# Pi_Zero_PITS.net
KiCad netlist of a schematic drawn in EAGLE
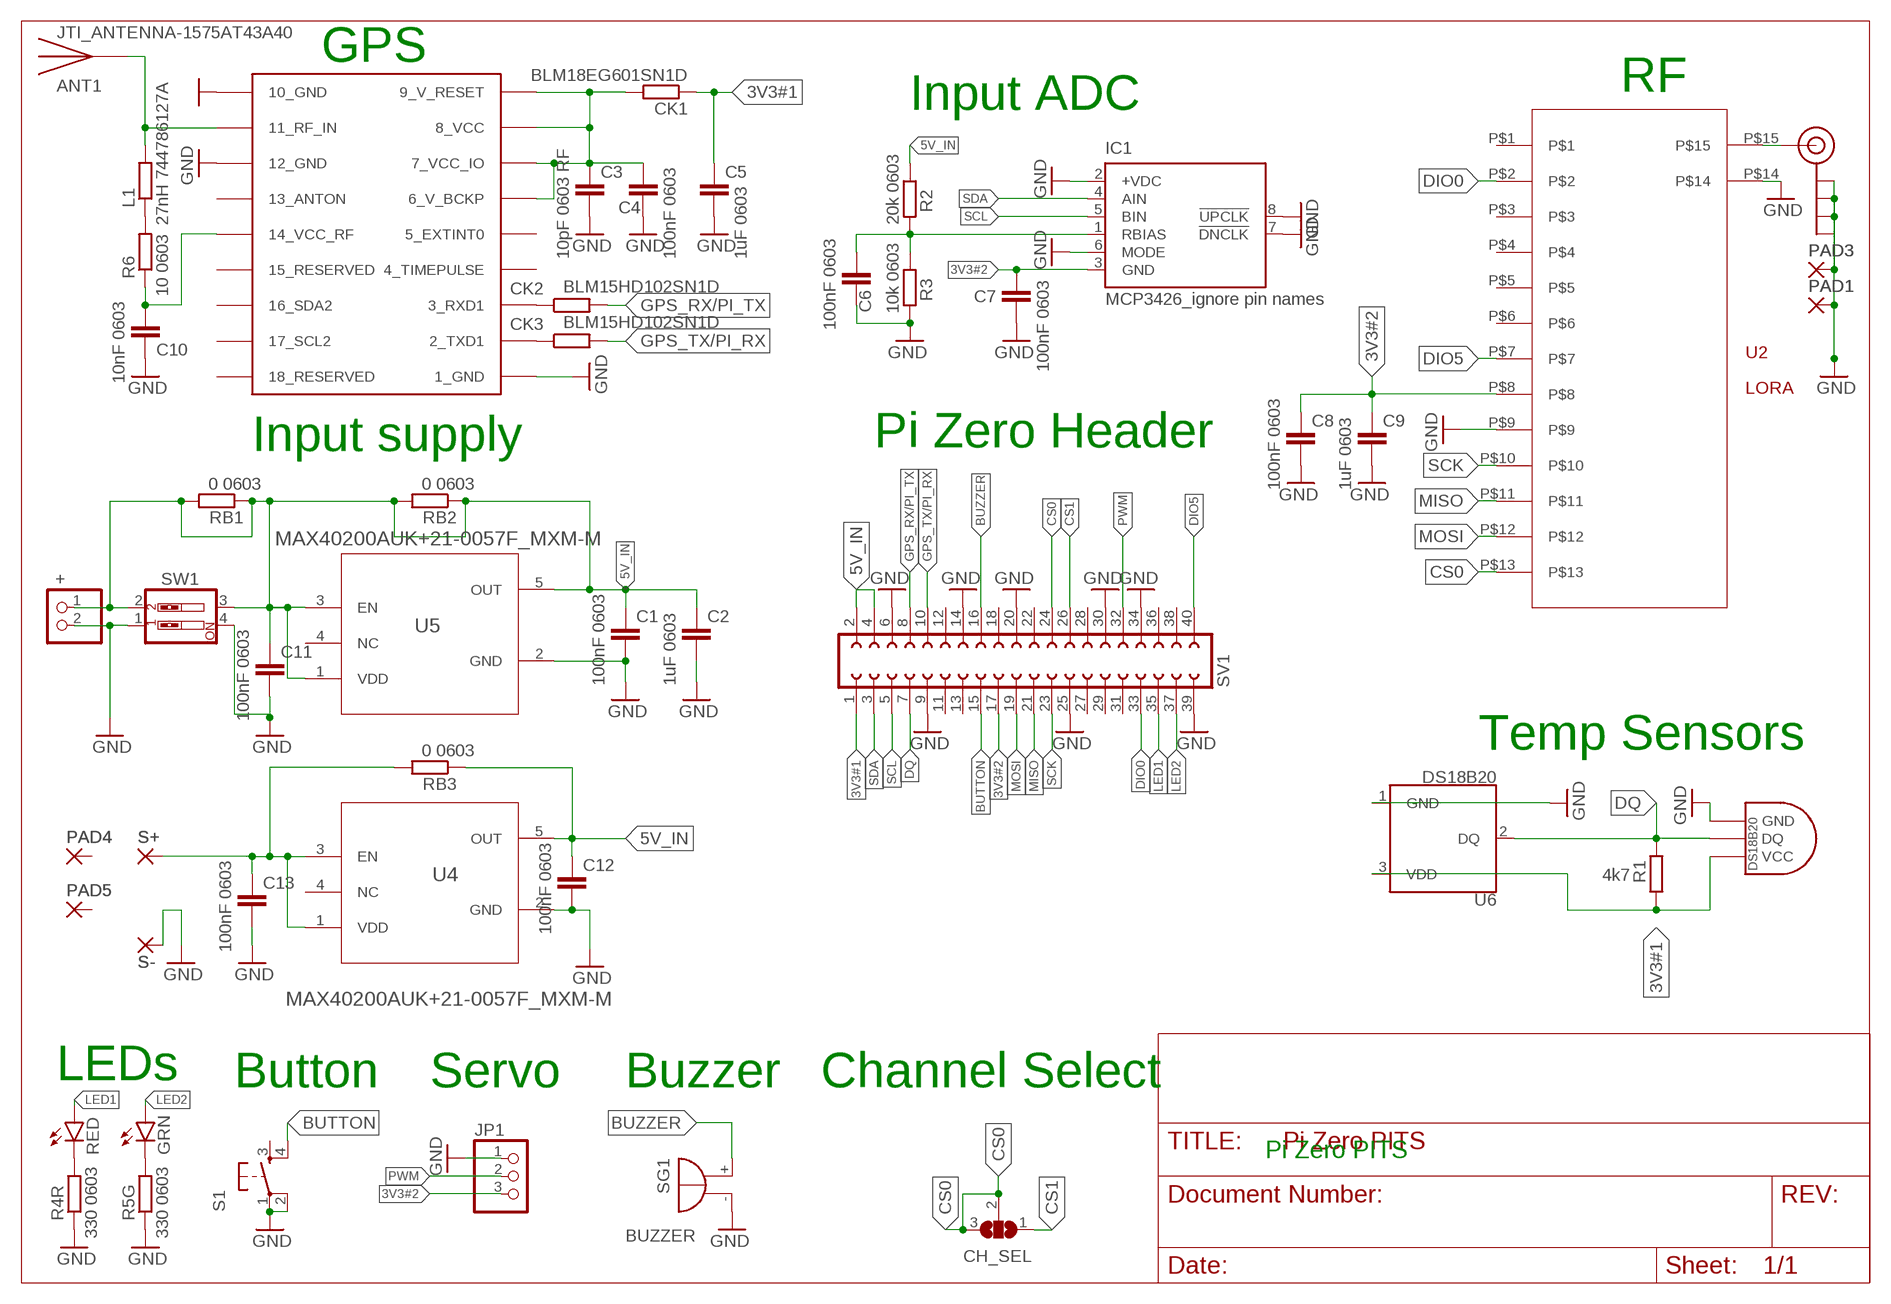
[diagram p0: schematic, sheet 1]

(export (version "E")
  (design (tool "Eeschema 10.0.6"))
  (components
    (comp (ref "+")
      (value "PINHD-1X2")
      (footprint "eagle-import:1X02")
      (libsource (lib "eagle-import") (part "PINHD-1X2"))
    )
    (comp (ref "18B20Z")
      (value "DS1820SOIC")
      (footprint "eagle-import:DS18B20_SOIC")
      (libsource (lib "eagle-import") (part "DS1820SOIC"))
    )
    (comp (ref "ANT1")
      (value "JTI_ANTENNA-1575AT43A40")
      (footprint "eagle-import:JTI_ANTENNA-1575AT43A40")
      (libsource (lib "eagle-import") (part "JTI_ANTENNA-1575AT43A40"))
    )
    (comp (ref "C1")
      (value "100nF 0603")
      (footprint "eagle-import:C0603K")
      (libsource (lib "eagle-import") (part "C-EUC0603K"))
    )
    (comp (ref "C2")
      (value "1uF 0603")
      (footprint "eagle-import:C0603K")
      (libsource (lib "eagle-import") (part "C-EUC0603K"))
    )
    (comp (ref "C3")
      (value "10pF 0603 RF")
      (footprint "eagle-import:C0603K")
      (libsource (lib "eagle-import") (part "C-EUC0603K"))
    )
    (comp (ref "C4")
      (value "100nF 0603")
      (footprint "eagle-import:C0603K")
      (libsource (lib "eagle-import") (part "C-EUC0603K"))
    )
    (comp (ref "C5")
      (value "1uF 0603")
      (footprint "eagle-import:C0603K")
      (libsource (lib "eagle-import") (part "C-EUC0603K"))
    )
    (comp (ref "C6")
      (value "100nF 0603")
      (footprint "eagle-import:C0603K")
      (libsource (lib "eagle-import") (part "C-EUC0603K"))
    )
    (comp (ref "C7")
      (value "100nF 0603")
      (footprint "eagle-import:C0603K")
      (libsource (lib "eagle-import") (part "C-EUC0603K"))
    )
    (comp (ref "C8")
      (value "100nF 0603")
      (footprint "eagle-import:C0603K")
      (libsource (lib "eagle-import") (part "C-EUC0603K"))
    )
    (comp (ref "C9")
      (value "1uF 0603")
      (footprint "eagle-import:C0603K")
      (libsource (lib "eagle-import") (part "C-EUC0603K"))
    )
    (comp (ref "C10")
      (value "10nF 0603")
      (footprint "eagle-import:C0603K")
      (libsource (lib "eagle-import") (part "C-EUC0603K"))
    )
    (comp (ref "C11")
      (value "100nF 0603")
      (footprint "eagle-import:C0603K")
      (libsource (lib "eagle-import") (part "C-EUC0603K"))
    )
    (comp (ref "C12")
      (value "100nF 0603")
      (footprint "eagle-import:C0603K")
      (libsource (lib "eagle-import") (part "C-EUC0603K"))
    )
    (comp (ref "C13")
      (value "100nF 0603")
      (footprint "eagle-import:C0603K")
      (libsource (lib "eagle-import") (part "C-EUC0603K"))
    )
    (comp (ref "CH_SEL")
      (value "SJ2W")
      (footprint "eagle-import:SJ_2")
      (libsource (lib "eagle-import") (part "SJ2W"))
    )
    (comp (ref "CK1")
      (value "BLM18EG601SN1D")
      (footprint "eagle-import:R0603")
      (libsource (lib "eagle-import") (part "R-EU_R0603"))
    )
    (comp (ref "CK2")
      (value "BLM15HD102SN1D")
      (footprint "eagle-import:R0402")
      (libsource (lib "eagle-import") (part "R-EU_R0402"))
    )
    (comp (ref "CK3")
      (value "BLM15HD102SN1D")
      (footprint "eagle-import:R0402")
      (libsource (lib "eagle-import") (part "R-EU_R0402"))
    )
    (comp (ref "GRN")
      (value "LEDSML0603")
      (footprint "eagle-import:SML0603")
      (libsource (lib "eagle-import") (part "LEDSML0603"))
    )
    (comp (ref "IC1")
      (value "MCP3426_ignore pin names")
      (footprint "eagle-import:SOIC08")
      (libsource (lib "eagle-import") (part "LS7183-SOIC"))
    )
    (comp (ref "J$2")
      (value "SMA_EDGE")
      (footprint "eagle-import:SMA-EDGE")
      (libsource (lib "eagle-import") (part "SMA_EDGE"))
    )
    (comp (ref "JP1")
      (value "PINHD-1X3")
      (footprint "eagle-import:1X03")
      (libsource (lib "eagle-import") (part "PINHD-1X3"))
    )
    (comp (ref "L1")
      (value "27nH 744786127A")
      (footprint "eagle-import:R0603")
      (libsource (lib "eagle-import") (part "R-EU_R0603"))
    )
    (comp (ref "PAD1")
      (value "SMD5")
      (footprint "eagle-import:SMD2,54-5,08")
      (libsource (lib "eagle-import") (part "SMD5"))
    )
    (comp (ref "PAD3")
      (value "SMD5")
      (footprint "eagle-import:SMD2,54-5,08")
      (libsource (lib "eagle-import") (part "SMD5"))
    )
    (comp (ref "PAD4")
      (value "SMD2SMD_KW")
      (footprint "eagle-import:SMD_SMALL")
      (libsource (lib "eagle-import") (part "SMD2SMD_KW"))
    )
    (comp (ref "PAD5")
      (value "SMD2SMD_KW")
      (footprint "eagle-import:SMD_SMALL")
      (libsource (lib "eagle-import") (part "SMD2SMD_KW"))
    )
    (comp (ref "R1")
      (value "4k7")
      (footprint "eagle-import:R0603")
      (libsource (lib "eagle-import") (part "R-EU_R0603"))
    )
    (comp (ref "R2")
      (value "20k 0603")
      (footprint "eagle-import:R0603")
      (libsource (lib "eagle-import") (part "R-EU_R0603"))
    )
    (comp (ref "R3")
      (value "10k 0603")
      (footprint "eagle-import:R0603")
      (libsource (lib "eagle-import") (part "R-EU_R0603"))
    )
    (comp (ref "R4R")
      (value "330 0603")
      (footprint "eagle-import:R0603")
      (libsource (lib "eagle-import") (part "R-EU_R0603"))
    )
    (comp (ref "R5G")
      (value "330 0603")
      (footprint "eagle-import:R0603")
      (libsource (lib "eagle-import") (part "R-EU_R0603"))
    )
    (comp (ref "R6")
      (value "10 0603")
      (footprint "eagle-import:R0603")
      (libsource (lib "eagle-import") (part "R-EU_R0603"))
    )
    (comp (ref "RB1")
      (value "0 0603")
      (footprint "eagle-import:R0603")
      (libsource (lib "eagle-import") (part "R-EU_R0603"))
    )
    (comp (ref "RB2")
      (value "0 0603")
      (footprint "eagle-import:R0603")
      (libsource (lib "eagle-import") (part "R-EU_R0603"))
    )
    (comp (ref "RB3")
      (value "0 0603")
      (footprint "eagle-import:R0603")
      (libsource (lib "eagle-import") (part "R-EU_R0603"))
    )
    (comp (ref "RED")
      (value "LEDSML0603")
      (footprint "eagle-import:SML0603")
      (libsource (lib "eagle-import") (part "LEDSML0603"))
    )
    (comp (ref "S+")
      (value "SMD2SMD_KW")
      (footprint "eagle-import:SMD_SMALL")
      (libsource (lib "eagle-import") (part "SMD2SMD_KW"))
    )
    (comp (ref "S-")
      (value "S-")
      (footprint "eagle-import:SMD_SMALL")
      (libsource (lib "eagle-import") (part "SMD2SMD_KW"))
    )
    (comp (ref "S1")
      (value "DTS-6")
      (footprint "eagle-import:DTS-6")
      (libsource (lib "eagle-import") (part "DTS-6"))
    )
    (comp (ref "SG1")
      (value "BUZZER")
      (footprint "eagle-import:BMT1205XH7.5")
      (libsource (lib "eagle-import") (part "BMT1205XH7.5"))
    )
    (comp (ref "SV1")
      (value "FE20-2")
      (footprint "eagle-import:FE20-2")
      (libsource (lib "eagle-import") (part "FE20-2"))
    )
    (comp (ref "SW1")
      (value "SW_DIP-2")
      (footprint "eagle-import:EDG-02")
      (libsource (lib "eagle-import") (part "SW_DIP-2"))
    )
    (comp (ref "U1")
      (value "U1")
      (footprint "eagle-import:UBLOX_MAX-6")
      (libsource (lib "eagle-import") (part "UBLOX_MAX-6"))
    )
    (comp (ref "U2")
      (value "LORA")
      (footprint "eagle-import:LORA_DRF")
      (libsource (lib "eagle-import") (part "LORA"))
    )
    (comp (ref "U4")
      (value "MAX40200AUK+21-0057F_MXM-M")
      (footprint "eagle-import:21-0057F_MXM-M")
      (fields
        (field (name "MANUFACTURER_PART_NUMBER") "MAX40200AUK+")
        (field (name "COPYRIGHT") "Copyright (C) 2018 Accelerated Designs. All rights reserved")
      )
      (libsource (lib "eagle-import") (part "MAX40200AUK+21-0057F_MXM-M"))
    )
    (comp (ref "U5")
      (value "MAX40200AUK+21-0057F_MXM-M")
      (footprint "eagle-import:21-0057F_MXM-M")
      (fields
        (field (name "MANUFACTURER_PART_NUMBER") "MAX40200AUK+")
        (field (name "COPYRIGHT") "Copyright (C) 2018 Accelerated Designs. All rights reserved")
      )
      (libsource (lib "eagle-import") (part "MAX40200AUK+21-0057F_MXM-M"))
    )
    (comp (ref "U6")
      (value "DS18B20")
      (footprint "eagle-import:TO-92-TO92127P495H2044-3")
      (fields (field (name "MF") "Maxim Integrated"))
      (libsource (lib "eagle-import") (part "DS18B20"))
    )
  )
  (nets
    (net (code "1") (name "3V3#1") (class "Default")
      (node (ref "18B20Z") (pin "VCC") (pinfunction "VCC_VCC") (pintype "power_in"))
      (node (ref "C5") (pin "1") (pinfunction "1_1") (pintype "passive"))
      (node (ref "CK1") (pin "1") (pinfunction "1_1") (pintype "passive"))
      (node (ref "R1") (pin "1") (pinfunction "1_1") (pintype "passive"))
      (node (ref "SV1") (pin "1") (pinfunction "1_1") (pintype "passive"))
      (node (ref "U6") (pin "3") (pinfunction "VDD_3") (pintype "power_in"))
    )
    (net (code "2") (name "3V3#2") (class "Default")
      (node (ref "C7") (pin "1") (pinfunction "1_1") (pintype "passive"))
      (node (ref "C8") (pin "1") (pinfunction "1_1") (pintype "passive"))
      (node (ref "C9") (pin "1") (pinfunction "1_1") (pintype "passive"))
      (node (ref "IC1") (pin "3") (pinfunction "GND_3") (pintype "power_in"))
      (node (ref "JP1") (pin "3") (pinfunction "3_3") (pintype "passive"))
      (node (ref "SV1") (pin "17") (pinfunction "17_17") (pintype "passive"))
      (node (ref "U2") (pin "P$8") (pinfunction "P$8_P$8") (pintype "bidirectional"))
    )
    (net (code "3") (name "5V_IN") (class "Default")
      (node (ref "+") (pin "1") (pinfunction "1_1") (pintype "passive"))
      (node (ref "C1") (pin "1") (pinfunction "1_1") (pintype "passive"))
      (node (ref "C11") (pin "1") (pinfunction "1_1") (pintype "passive"))
      (node (ref "C12") (pin "1") (pinfunction "1_1") (pintype "passive"))
      (node (ref "C2") (pin "1") (pinfunction "1_1") (pintype "passive"))
      (node (ref "R2") (pin "1") (pinfunction "1_1") (pintype "passive"))
      (node (ref "RB1") (pin "1") (pinfunction "1_1") (pintype "passive"))
      (node (ref "RB1") (pin "2") (pinfunction "2_2") (pintype "passive"))
      (node (ref "RB2") (pin "1") (pinfunction "1_1") (pintype "passive"))
      (node (ref "RB2") (pin "2") (pinfunction "2_2") (pintype "passive"))
      (node (ref "RB3") (pin "1") (pinfunction "1_1") (pintype "passive"))
      (node (ref "SV1") (pin "2") (pinfunction "2_2") (pintype "passive"))
      (node (ref "SV1") (pin "4") (pinfunction "4_4") (pintype "passive"))
      (node (ref "SW1") (pin "2") (pinfunction "2_2") (pintype "passive"))
      (node (ref "SW1") (pin "3") (pinfunction "3_3") (pintype "passive"))
      (node (ref "U4") (pin "5") (pinfunction "OUT_5") (pintype "output"))
      (node (ref "U5") (pin "1") (pinfunction "VDD_1") (pintype "power_in"))
      (node (ref "U5") (pin "3") (pinfunction "EN_3") (pintype "passive"))
      (node (ref "U5") (pin "5") (pinfunction "OUT_5") (pintype "output"))
    )
    (net (code "4") (name "BUTTON") (class "Default")
      (node (ref "S1") (pin "4") (pinfunction "4_4") (pintype "passive"))
      (node (ref "SV1") (pin "15") (pinfunction "15_15") (pintype "passive"))
    )
    (net (code "5") (name "BUZZER") (class "Default")
      (node (ref "SG1") (pin "+") (pinfunction "+_+") (pintype "passive"))
      (node (ref "SV1") (pin "16") (pinfunction "16_16") (pintype "passive"))
    )
    (net (code "6") (name "CS0") (class "Default")
      (node (ref "CH_SEL") (pin "2") (pinfunction "2_2") (pintype "passive"))
      (node (ref "CH_SEL") (pin "3") (pinfunction "3_3") (pintype "passive"))
      (node (ref "SV1") (pin "24") (pinfunction "24_24") (pintype "passive"))
      (node (ref "U2") (pin "P$13") (pinfunction "P$13_P$13") (pintype "bidirectional"))
    )
    (net (code "7") (name "CS1") (class "Default")
      (node (ref "CH_SEL") (pin "1") (pinfunction "1_1") (pintype "passive"))
      (node (ref "SV1") (pin "26") (pinfunction "26_26") (pintype "passive"))
    )
    (net (code "8") (name "DIO0") (class "Default")
      (node (ref "SV1") (pin "33") (pinfunction "33_33") (pintype "passive"))
      (node (ref "U2") (pin "P$2") (pinfunction "P$2_P$2") (pintype "bidirectional"))
    )
    (net (code "9") (name "DIO5") (class "Default")
      (node (ref "SV1") (pin "40") (pinfunction "40_40") (pintype "passive"))
      (node (ref "U2") (pin "P$7") (pinfunction "P$7_P$7") (pintype "bidirectional"))
    )
    (net (code "10") (name "DQ") (class "Default")
      (node (ref "18B20Z") (pin "DQ") (pinfunction "DQ_DQ") (pintype "bidirectional"))
      (node (ref "R1") (pin "2") (pinfunction "2_2") (pintype "passive"))
      (node (ref "SV1") (pin "7") (pinfunction "7_7") (pintype "passive"))
      (node (ref "U6") (pin "2") (pinfunction "DQ_2") (pintype "bidirectional"))
    )
    (net (code "11") (name "GND") (class "Default")
      (node (ref "+") (pin "2") (pinfunction "2_2") (pintype "passive"))
      (node (ref "18B20Z") (pin "GND") (pinfunction "GND_GND") (pintype "power_in"))
      (node (ref "C1") (pin "2") (pinfunction "2_2") (pintype "passive"))
      (node (ref "C10") (pin "2") (pinfunction "2_2") (pintype "passive"))
      (node (ref "C11") (pin "2") (pinfunction "2_2") (pintype "passive"))
      (node (ref "C12") (pin "2") (pinfunction "2_2") (pintype "passive"))
      (node (ref "C13") (pin "2") (pinfunction "2_2") (pintype "passive"))
      (node (ref "C2") (pin "2") (pinfunction "2_2") (pintype "passive"))
      (node (ref "C3") (pin "2") (pinfunction "2_2") (pintype "passive"))
      (node (ref "C4") (pin "2") (pinfunction "2_2") (pintype "passive"))
      (node (ref "C5") (pin "2") (pinfunction "2_2") (pintype "passive"))
      (node (ref "C6") (pin "2") (pinfunction "2_2") (pintype "passive"))
      (node (ref "C7") (pin "2") (pinfunction "2_2") (pintype "passive"))
      (node (ref "C8") (pin "2") (pinfunction "2_2") (pintype "passive"))
      (node (ref "C9") (pin "2") (pinfunction "2_2") (pintype "passive"))
      (node (ref "IC1") (pin "2") (pinfunction "+VDC_2") (pintype "input"))
      (node (ref "IC1") (pin "6") (pinfunction "MODE_6") (pintype "input"))
      (node (ref "IC1") (pin "7") (pinfunction "~{DNCLK}_7") (pintype "input"))
      (node (ref "IC1") (pin "8") (pinfunction "~{UPCLK}_8") (pintype "input"))
      (node (ref "J$2") (pin "GND@0") (pinfunction "GND_GND@0") (pintype "bidirectional"))
      (node (ref "J$2") (pin "GND@1") (pinfunction "GND_GND@1") (pintype "bidirectional"))
      (node (ref "J$2") (pin "GND@2") (pinfunction "GND_GND@2") (pintype "bidirectional"))
      (node (ref "J$2") (pin "GND@3") (pinfunction "GND_GND@3") (pintype "bidirectional"))
      (node (ref "JP1") (pin "1") (pinfunction "1_1") (pintype "passive"))
      (node (ref "PAD1") (pin "1") (pinfunction "P_1") (pintype "passive"))
      (node (ref "PAD3") (pin "1") (pinfunction "P_1") (pintype "passive"))
      (node (ref "R3") (pin "2") (pinfunction "2_2") (pintype "passive"))
      (node (ref "R4R") (pin "1") (pinfunction "1_1") (pintype "passive"))
      (node (ref "R5G") (pin "1") (pinfunction "1_1") (pintype "passive"))
      (node (ref "S-") (pin "1") (pinfunction "P_1") (pintype "passive"))
      (node (ref "S1") (pin "1") (pinfunction "1_1") (pintype "passive"))
      (node (ref "S1") (pin "2") (pinfunction "2_2") (pintype "passive"))
      (node (ref "SG1") (pin "-") (pinfunction "-_-") (pintype "passive"))
      (node (ref "SV1") (pin "14") (pinfunction "14_14") (pintype "passive"))
      (node (ref "SV1") (pin "20") (pinfunction "20_20") (pintype "passive"))
      (node (ref "SV1") (pin "25") (pinfunction "25_25") (pintype "passive"))
      (node (ref "SV1") (pin "30") (pinfunction "30_30") (pintype "passive"))
      (node (ref "SV1") (pin "34") (pinfunction "34_34") (pintype "passive"))
      (node (ref "SV1") (pin "39") (pinfunction "39_39") (pintype "passive"))
      (node (ref "SV1") (pin "6") (pinfunction "6_6") (pintype "passive"))
      (node (ref "SV1") (pin "9") (pinfunction "9_9") (pintype "passive"))
      (node (ref "SW1") (pin "1") (pinfunction "1_1") (pintype "passive"))
      (node (ref "SW1") (pin "4") (pinfunction "4_4") (pintype "passive"))
      (node (ref "U1") (pin "10_GND") (pinfunction "10_GND_10_GND") (pintype "power_in"))
      (node (ref "U1") (pin "12_GND") (pinfunction "12_GND_12_GND") (pintype "power_in"))
      (node (ref "U1") (pin "1_GND") (pinfunction "1_GND_1_GND") (pintype "power_in"))
      (node (ref "U2") (pin "P$14") (pinfunction "P$14_P$14") (pintype "bidirectional"))
      (node (ref "U2") (pin "P$9") (pinfunction "P$9_P$9") (pintype "bidirectional"))
      (node (ref "U4") (pin "2") (pinfunction "GND_2") (pintype "passive"))
      (node (ref "U5") (pin "2") (pinfunction "GND_2") (pintype "passive"))
      (node (ref "U6") (pin "1") (pinfunction "GND_1") (pintype "power_in"))
    )
    (net (code "12") (name "GPS_RX{slash}PI_TX") (class "Default")
      (node (ref "CK2") (pin "2") (pinfunction "2_2") (pintype "passive"))
      (node (ref "SV1") (pin "8") (pinfunction "8_8") (pintype "passive"))
    )
    (net (code "13") (name "GPS_TX{slash}PI_RX") (class "Default")
      (node (ref "CK3") (pin "2") (pinfunction "2_2") (pintype "passive"))
      (node (ref "SV1") (pin "10") (pinfunction "10_10") (pintype "passive"))
    )
    (net (code "14") (name "LED1") (class "Default")
      (node (ref "RED") (pin "A") (pinfunction "A_A") (pintype "passive"))
      (node (ref "SV1") (pin "35") (pinfunction "35_35") (pintype "passive"))
    )
    (net (code "15") (name "LED2") (class "Default")
      (node (ref "GRN") (pin "A") (pinfunction "A_A") (pintype "passive"))
      (node (ref "SV1") (pin "37") (pinfunction "37_37") (pintype "passive"))
    )
    (net (code "16") (name "MISO") (class "Default")
      (node (ref "SV1") (pin "21") (pinfunction "21_21") (pintype "passive"))
      (node (ref "U2") (pin "P$11") (pinfunction "P$11_P$11") (pintype "bidirectional"))
    )
    (net (code "17") (name "MOSI") (class "Default")
      (node (ref "SV1") (pin "19") (pinfunction "19_19") (pintype "passive"))
      (node (ref "U2") (pin "P$12") (pinfunction "P$12_P$12") (pintype "bidirectional"))
    )
    (net (code "18") (name "Net-(ANT1-PadFEED)") (class "Default")
      (node (ref "ANT1") (pin "FEED") (pinfunction "FEED_FEED") (pintype "bidirectional"))
      (node (ref "L1") (pin "2") (pinfunction "2_2") (pintype "passive"))
      (node (ref "U1") (pin "11_RF_IN") (pinfunction "11_RF_IN_11_RF_IN") (pintype "bidirectional"))
    )
    (net (code "19") (name "Net-(C3-Pad1)") (class "Default")
      (node (ref "C3") (pin "1") (pinfunction "1_1") (pintype "passive"))
      (node (ref "C4") (pin "1") (pinfunction "1_1") (pintype "passive"))
      (node (ref "CK1") (pin "2") (pinfunction "2_2") (pintype "passive"))
      (node (ref "U1") (pin "6_V_BCKP") (pinfunction "6_V_BCKP_6_V_BCKP") (pintype "bidirectional"))
      (node (ref "U1") (pin "7_VCC_IO") (pinfunction "7_VCC_IO_7_VCC_IO") (pintype "power_in"))
      (node (ref "U1") (pin "8_VCC") (pinfunction "8_VCC_8_VCC") (pintype "power_in"))
      (node (ref "U1") (pin "9_V_RESET") (pinfunction "9_V_RESET_9_V_RESET") (pintype "power_in"))
    )
    (net (code "20") (name "Net-(C10-Pad1)") (class "Default")
      (node (ref "C10") (pin "1") (pinfunction "1_1") (pintype "passive"))
      (node (ref "R6") (pin "1") (pinfunction "1_1") (pintype "passive"))
      (node (ref "U1") (pin "14_VCC_RF") (pinfunction "14_VCC_RF_14_VCC_RF") (pintype "bidirectional"))
    )
    (net (code "21") (name "Net-(CK2-Pad1)") (class "Default")
      (node (ref "CK2") (pin "1") (pinfunction "1_1") (pintype "passive"))
      (node (ref "U1") (pin "3_RXD1") (pinfunction "3_RXD1_3_RXD1") (pintype "bidirectional"))
    )
    (net (code "22") (name "Net-(CK3-Pad1)") (class "Default")
      (node (ref "CK3") (pin "1") (pinfunction "1_1") (pintype "passive"))
      (node (ref "U1") (pin "2_TXD1") (pinfunction "2_TXD1_2_TXD1") (pintype "bidirectional"))
    )
    (net (code "23") (name "Net-(GRN-PadC)") (class "Default")
      (node (ref "GRN") (pin "C") (pinfunction "C_C") (pintype "passive"))
      (node (ref "R5G") (pin "2") (pinfunction "2_2") (pintype "passive"))
    )
    (net (code "24") (name "Net-(IC1-RBIAS)") (class "Default")
      (node (ref "C6") (pin "1") (pinfunction "1_1") (pintype "passive"))
      (node (ref "IC1") (pin "1") (pinfunction "RBIAS_1") (pintype "input"))
      (node (ref "R2") (pin "2") (pinfunction "2_2") (pintype "passive"))
      (node (ref "R3") (pin "1") (pinfunction "1_1") (pintype "passive"))
    )
    (net (code "25") (name "Net-(J$2-SIGNAL)") (class "Default")
      (node (ref "J$2") (pin "SIG") (pinfunction "SIGNAL_SIG") (pintype "bidirectional"))
      (node (ref "U2") (pin "P$15") (pinfunction "P$15_P$15") (pintype "bidirectional"))
    )
    (net (code "26") (name "Net-(L1-Pad1)") (class "Default")
      (node (ref "L1") (pin "1") (pinfunction "1_1") (pintype "passive"))
      (node (ref "R6") (pin "2") (pinfunction "2_2") (pintype "passive"))
    )
    (net (code "27") (name "Net-(R4R-Pad2)") (class "Default")
      (node (ref "R4R") (pin "2") (pinfunction "2_2") (pintype "passive"))
      (node (ref "RED") (pin "C") (pinfunction "C_C") (pintype "passive"))
    )
    (net (code "28") (name "Net-(S+-P)") (class "Default")
      (node (ref "C13") (pin "1") (pinfunction "1_1") (pintype "passive"))
      (node (ref "RB3") (pin "2") (pinfunction "2_2") (pintype "passive"))
      (node (ref "S+") (pin "1") (pinfunction "P_1") (pintype "passive"))
      (node (ref "U4") (pin "1") (pinfunction "VDD_1") (pintype "power_in"))
      (node (ref "U4") (pin "3") (pinfunction "EN_3") (pintype "passive"))
    )
    (net (code "29") (name "PWM") (class "Default")
      (node (ref "JP1") (pin "2") (pinfunction "2_2") (pintype "passive"))
      (node (ref "SV1") (pin "32") (pinfunction "32_32") (pintype "passive"))
    )
    (net (code "30") (name "SCK") (class "Default")
      (node (ref "SV1") (pin "23") (pinfunction "23_23") (pintype "passive"))
      (node (ref "U2") (pin "P$10") (pinfunction "P$10_P$10") (pintype "bidirectional"))
    )
    (net (code "31") (name "SCL") (class "Default")
      (node (ref "IC1") (pin "5") (pinfunction "BIN_5") (pintype "input"))
      (node (ref "SV1") (pin "5") (pinfunction "5_5") (pintype "passive"))
    )
    (net (code "32") (name "SDA") (class "Default")
      (node (ref "IC1") (pin "4") (pinfunction "AIN_4") (pintype "input"))
      (node (ref "SV1") (pin "3") (pinfunction "3_3") (pintype "passive"))
    )
    (net (code "33") (name "unconnected-(PAD4-P-Pad1)") (class "Default")
      (node (ref "PAD4") (pin "1") (pinfunction "P_1") (pintype "passive"))
    )
    (net (code "34") (name "unconnected-(PAD5-P-Pad1)") (class "Default")
      (node (ref "PAD5") (pin "1") (pinfunction "P_1") (pintype "passive"))
    )
    (net (code "35") (name "unconnected-(S1-Pad3)") (class "Default")
      (node (ref "S1") (pin "3") (pinfunction "3_3") (pintype "passive"))
    )
    (net (code "36") (name "unconnected-(SV1-Pad11)") (class "Default")
      (node (ref "SV1") (pin "11") (pinfunction "11_11") (pintype "passive"))
    )
    (net (code "37") (name "unconnected-(SV1-Pad12)") (class "Default")
      (node (ref "SV1") (pin "12") (pinfunction "12_12") (pintype "passive"))
    )
    (net (code "38") (name "unconnected-(SV1-Pad13)") (class "Default")
      (node (ref "SV1") (pin "13") (pinfunction "13_13") (pintype "passive"))
    )
    (net (code "39") (name "unconnected-(SV1-Pad18)") (class "Default")
      (node (ref "SV1") (pin "18") (pinfunction "18_18") (pintype "passive"))
    )
    (net (code "40") (name "unconnected-(SV1-Pad22)") (class "Default")
      (node (ref "SV1") (pin "22") (pinfunction "22_22") (pintype "passive"))
    )
    (net (code "41") (name "unconnected-(SV1-Pad27)") (class "Default")
      (node (ref "SV1") (pin "27") (pinfunction "27_27") (pintype "passive"))
    )
    (net (code "42") (name "unconnected-(SV1-Pad28)") (class "Default")
      (node (ref "SV1") (pin "28") (pinfunction "28_28") (pintype "passive"))
    )
    (net (code "43") (name "unconnected-(SV1-Pad29)") (class "Default")
      (node (ref "SV1") (pin "29") (pinfunction "29_29") (pintype "passive"))
    )
    (net (code "44") (name "unconnected-(SV1-Pad31)") (class "Default")
      (node (ref "SV1") (pin "31") (pinfunction "31_31") (pintype "passive"))
    )
    (net (code "45") (name "unconnected-(SV1-Pad36)") (class "Default")
      (node (ref "SV1") (pin "36") (pinfunction "36_36") (pintype "passive"))
    )
    (net (code "46") (name "unconnected-(SV1-Pad38)") (class "Default")
      (node (ref "SV1") (pin "38") (pinfunction "38_38") (pintype "passive"))
    )
    (net (code "47") (name "unconnected-(U1-Pad4_TIMEPULSE)") (class "Default")
      (node (ref "U1") (pin "4_TIMEPULSE") (pinfunction "4_TIMEPULSE_4_TIMEPULSE") (pintype "bidirectional"))
    )
    (net (code "48") (name "unconnected-(U1-Pad5_EXTINT0)") (class "Default")
      (node (ref "U1") (pin "5_EXTINT0") (pinfunction "5_EXTINT0_5_EXTINT0") (pintype "bidirectional"))
    )
    (net (code "49") (name "unconnected-(U1-Pad13_ANTON)") (class "Default")
      (node (ref "U1") (pin "13_ANTON") (pinfunction "13_ANTON_13_ANTON") (pintype "bidirectional"))
    )
    (net (code "50") (name "unconnected-(U1-Pad15_RESERVED)") (class "Default")
      (node (ref "U1") (pin "15_RESERVED") (pinfunction "15_RESERVED_15_RESERVED") (pintype "bidirectional"))
    )
    (net (code "51") (name "unconnected-(U1-Pad16_SDA2)") (class "Default")
      (node (ref "U1") (pin "16_SDA2") (pinfunction "16_SDA2_16_SDA2") (pintype "bidirectional"))
    )
    (net (code "52") (name "unconnected-(U1-Pad17_SCL2)") (class "Default")
      (node (ref "U1") (pin "17_SCL2") (pinfunction "17_SCL2_17_SCL2") (pintype "bidirectional"))
    )
    (net (code "53") (name "unconnected-(U1-Pad18_RESERVED)") (class "Default")
      (node (ref "U1") (pin "18_RESERVED") (pinfunction "18_RESERVED_18_RESERVED") (pintype "bidirectional"))
    )
    (net (code "54") (name "unconnected-(U2-PadP$1)") (class "Default")
      (node (ref "U2") (pin "P$1") (pinfunction "P$1_P$1") (pintype "bidirectional"))
    )
    (net (code "55") (name "unconnected-(U2-PadP$3)") (class "Default")
      (node (ref "U2") (pin "P$3") (pinfunction "P$3_P$3") (pintype "bidirectional"))
    )
    (net (code "56") (name "unconnected-(U2-PadP$4)") (class "Default")
      (node (ref "U2") (pin "P$4") (pinfunction "P$4_P$4") (pintype "bidirectional"))
    )
    (net (code "57") (name "unconnected-(U2-PadP$5)") (class "Default")
      (node (ref "U2") (pin "P$5") (pinfunction "P$5_P$5") (pintype "bidirectional"))
    )
    (net (code "58") (name "unconnected-(U2-PadP$6)") (class "Default")
      (node (ref "U2") (pin "P$6") (pinfunction "P$6_P$6") (pintype "bidirectional"))
    )
    (net (code "59") (name "unconnected-(U4-NC-Pad4)") (class "Default")
      (node (ref "U4") (pin "4") (pinfunction "NC_4") (pintype "no_connect"))
    )
    (net (code "60") (name "unconnected-(U5-NC-Pad4)") (class "Default")
      (node (ref "U5") (pin "4") (pinfunction "NC_4") (pintype "no_connect"))
    )
  )
)
